# FeatherRemoteReceiverFullSMD.net
KiCad netlist of a schematic drawn in EAGLE
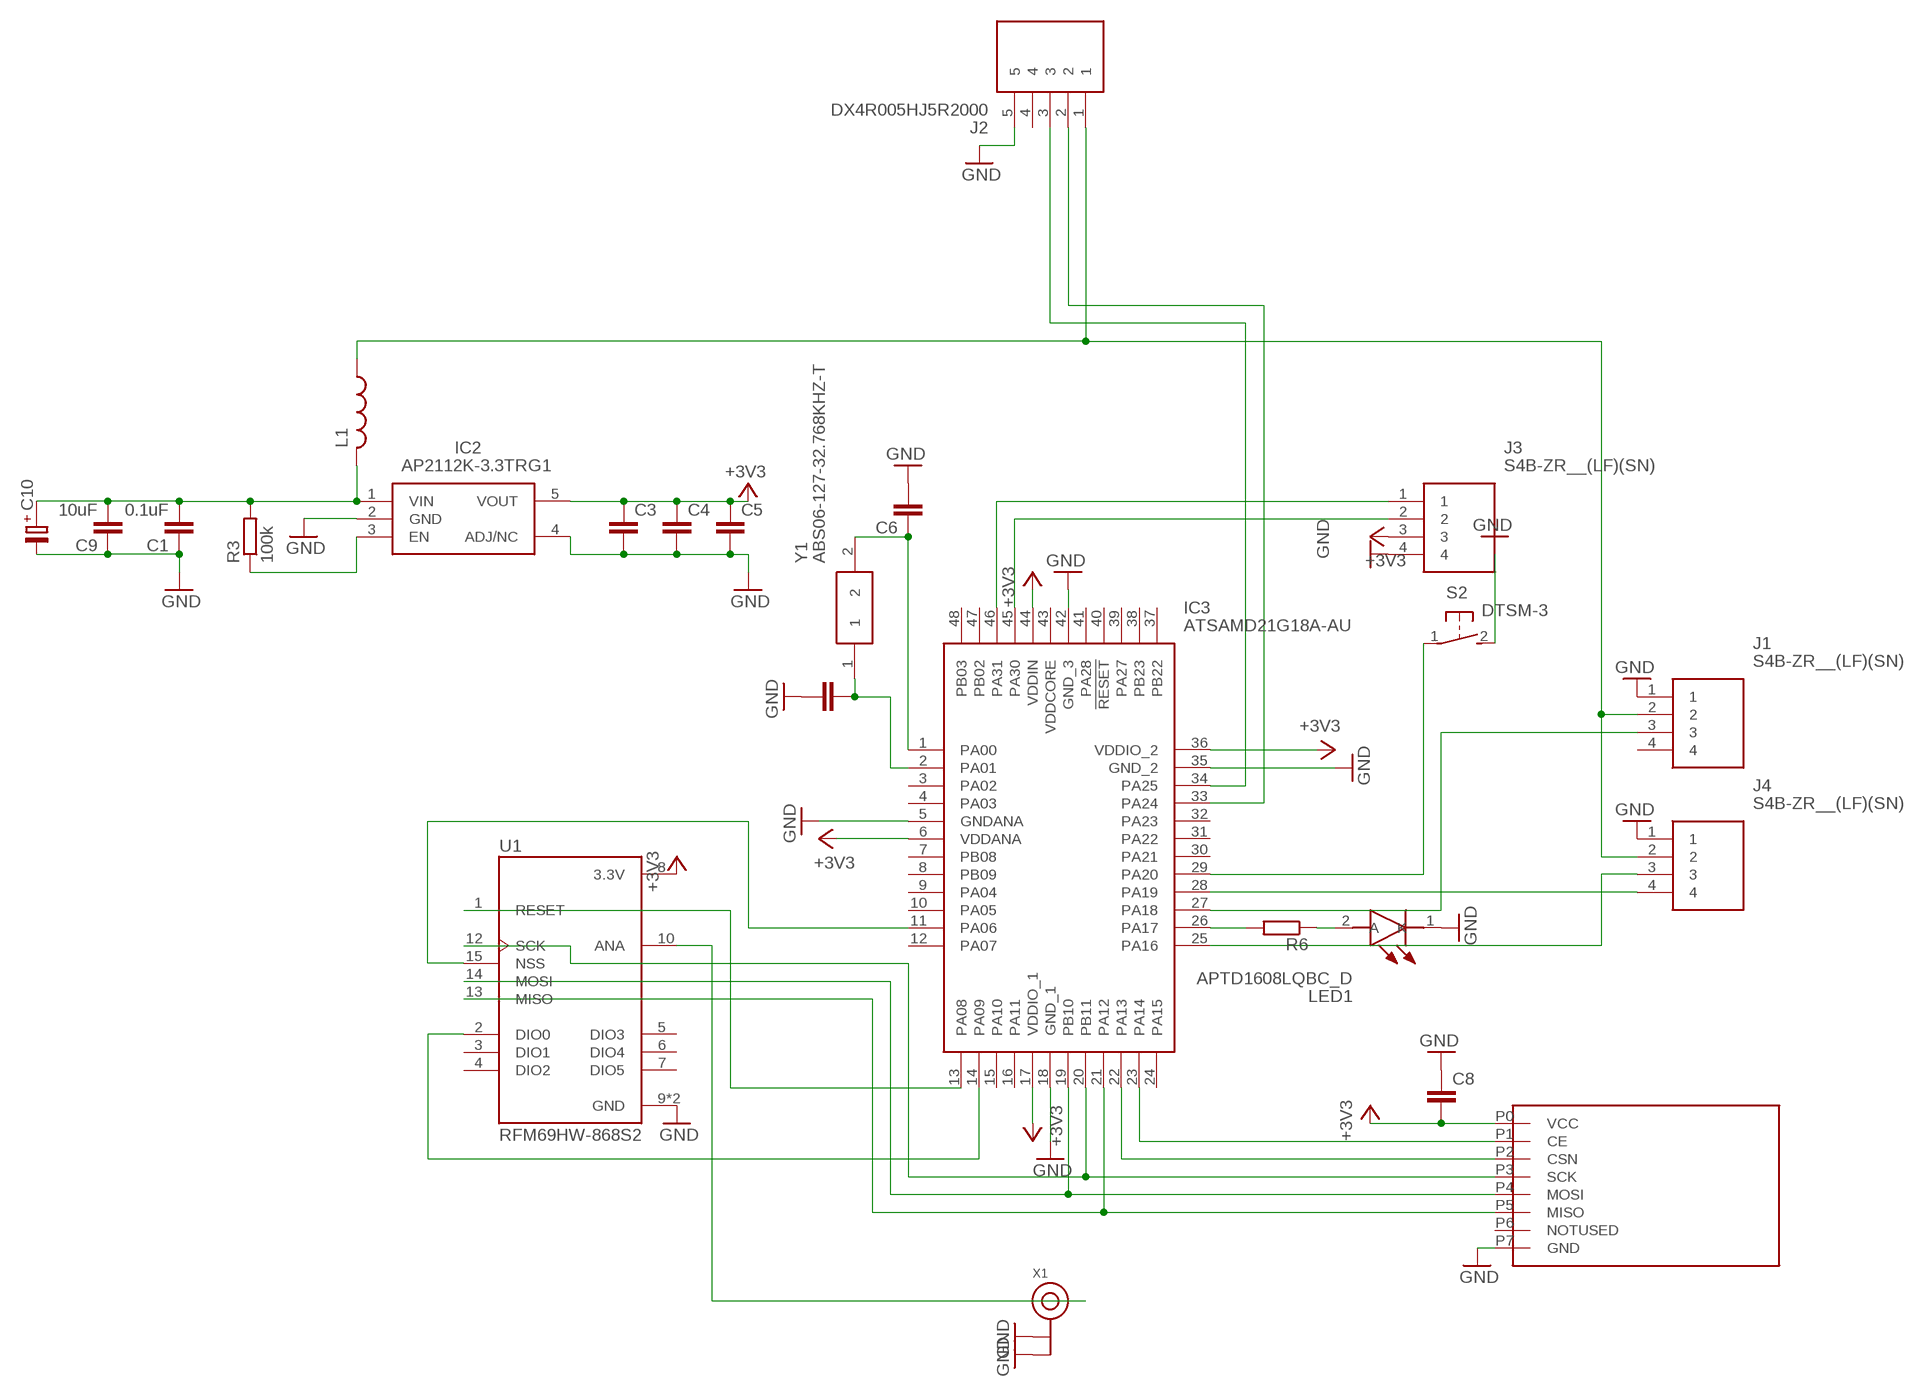
[diagram p0: schematic, sheet 1]

(export (version "E")
  (design (tool "Eeschema 10.0.6"))
  (components
    (comp (ref "C1")
      (value "0.1uF")
      (footprint "eagle-import:C0603")
      (libsource (lib "eagle-import") (part "C-EUC0603"))
    )
    (comp (ref "C3")
      (value "C-EUC0603")
      (footprint "eagle-import:C0603")
      (libsource (lib "eagle-import") (part "C-EUC0603"))
    )
    (comp (ref "C4")
      (value "C-EUC0603")
      (footprint "eagle-import:C0603")
      (libsource (lib "eagle-import") (part "C-EUC0603"))
    )
    (comp (ref "C5")
      (value "C-EUC0603")
      (footprint "eagle-import:C0603")
      (libsource (lib "eagle-import") (part "C-EUC0603"))
    )
    (comp (ref "C6")
      (value "C-EUC0603")
      (footprint "eagle-import:C0603")
      (libsource (lib "eagle-import") (part "C-EUC0603"))
    )
    (comp (ref "C7")
      (value "C-EUC0603")
      (footprint "eagle-import:C0603")
      (libsource (lib "eagle-import") (part "C-EUC0603"))
    )
    (comp (ref "C8")
      (value "C-EUC0603")
      (footprint "eagle-import:C0603")
      (libsource (lib "eagle-import") (part "C-EUC0603"))
    )
    (comp (ref "C9")
      (value "10uF")
      (footprint "eagle-import:C0603")
      (libsource (lib "eagle-import") (part "C-EUC0603"))
    )
    (comp (ref "C10")
      (value "C-PR-SMD-TE-D")
      (footprint "eagle-import:TE-D-7343")
      (libsource (lib "eagle-import") (part "C-PR-SMD-TE-D"))
    )
    (comp (ref "IC2")
      (value "AP2112K-3.3TRG1")
      (footprint "eagle-import:SOT95P282X130-5N")
      (fields (field (name "MOUSER_PART_NUMBER") "621-AP2112K-3.3TRG1"))
      (libsource (lib "eagle-import") (part "AP2112K-3.3TRG1"))
    )
    (comp (ref "IC3")
      (value "ATSAMD21G18A-AU")
      (footprint "eagle-import:QFP50P900X900X120-48N")
      (fields (field (name "MOUSER_PART_NUMBER") "556-ATSAMD21G18A-AU"))
      (libsource (lib "eagle-import") (part "ATSAMD21G18A-AU"))
    )
    (comp (ref "J1")
      (value "S4B-ZR__(LF)(SN)")
      (footprint "eagle-import:SHDR4W50P0X150_1X4_750X600X370")
      (fields (field (name "MANUFACTURER_PART_NUMBER") "S4B-ZR  (LF)(SN)"))
      (libsource (lib "eagle-import") (part "S4B-ZR__(LF)(SN)"))
    )
    (comp (ref "J2")
      (value "DX4R005HJ5R2000")
      (footprint "eagle-import:DX4R005HJ5")
      (fields (field (name "MOUSER_PART_NUMBER") "656-DX4R005HJ5R2000"))
      (libsource (lib "eagle-import") (part "DX4R005HJ5R2000"))
    )
    (comp (ref "J3")
      (value "S4B-ZR__(LF)(SN)")
      (footprint "eagle-import:SHDR4W50P0X150_1X4_750X600X370")
      (fields (field (name "MANUFACTURER_PART_NUMBER") "S4B-ZR  (LF)(SN)"))
      (libsource (lib "eagle-import") (part "S4B-ZR__(LF)(SN)"))
    )
    (comp (ref "J4")
      (value "S4B-ZR__(LF)(SN)")
      (footprint "eagle-import:SHDR4W50P0X150_1X4_750X600X370")
      (fields (field (name "MANUFACTURER_PART_NUMBER") "S4B-ZR  (LF)(SN)"))
      (libsource (lib "eagle-import") (part "S4B-ZR__(LF)(SN)"))
    )
    (comp (ref "L1")
      (value "L-USL1812")
      (footprint "eagle-import:L1812")
      (libsource (lib "eagle-import") (part "L-USL1812"))
    )
    (comp (ref "LED1")
      (value "APTD1608LQBC_D")
      (footprint "eagle-import:LEDC1608X95N")
      (fields
        (field (name "MANUFACTURER_PART_NUMBER") "APTD1608LQBC/D")
        (field (name "MOUSER_PART_NUMBER") "604-APTD1608LQBCD")
      )
      (libsource (lib "eagle-import") (part "APTD1608LQBC_D"))
    )
    (comp (ref "R3")
      (value "100k")
      (footprint "eagle-import:R0603")
      (libsource (lib "eagle-import") (part "R-EU_R0603"))
    )
    (comp (ref "R6")
      (value "R-EU_R0603")
      (footprint "eagle-import:R0603")
      (libsource (lib "eagle-import") (part "R-EU_R0603"))
    )
    (comp (ref "S2")
      (value "DTSM-3")
      (footprint "eagle-import:DTSM-3")
      (libsource (lib "eagle-import") (part "DTSM-3"))
    )
    (comp (ref "U$2")
      (value "NRF24L01PA")
      (footprint "eagle-import:NRF24L01PA")
      (libsource (lib "eagle-import") (part "NRF24L01PA"))
    )
    (comp (ref "U1")
      (value "RFM69HW-868S2")
      (footprint "eagle-import:XCVR_RFM69HW-868S2")
      (fields (field (name "MF") "RF"))
      (libsource (lib "eagle-import") (part "RFM69HW-868S2"))
    )
    (comp (ref "X1")
      (value "ANTENNA_U.FL")
      (footprint "eagle-import:U.FL")
      (libsource (lib "eagle-import") (part "ANTENNA_U.FL"))
    )
    (comp (ref "Y1")
      (value "ABS06-127-32.768KHZ-T")
      (footprint "eagle-import:ABS0612732768KHZT")
      (fields (field (name "MOUSER_PART_NUMBER") "815-ABS0612732.768KT"))
      (libsource (lib "eagle-import") (part "ABS06-127-32.768KHZ-T"))
    )
  )
  (nets
    (net (code "1") (name "+3V3") (class "Default")
      (node (ref "C3") (pin "1") (pinfunction "1_1") (pintype "passive"))
      (node (ref "C4") (pin "1") (pinfunction "1_1") (pintype "passive"))
      (node (ref "C5") (pin "1") (pinfunction "1_1") (pintype "passive"))
      (node (ref "C8") (pin "2") (pinfunction "2_2") (pintype "passive"))
      (node (ref "IC2") (pin "5") (pinfunction "VOUT_5") (pintype "bidirectional"))
      (node (ref "IC3") (pin "17") (pinfunction "VDDIO_1_17") (pintype "bidirectional"))
      (node (ref "IC3") (pin "36") (pinfunction "VDDIO_2_36") (pintype "bidirectional"))
      (node (ref "IC3") (pin "44") (pinfunction "VDDIN_44") (pintype "bidirectional"))
      (node (ref "IC3") (pin "6") (pinfunction "VDDANA_6") (pintype "bidirectional"))
      (node (ref "J3") (pin "3") (pinfunction "3_3") (pintype "bidirectional"))
      (node (ref "U$2") (pin "P0") (pinfunction "VCC_P0") (pintype "bidirectional"))
      (node (ref "U1") (pin "8") (pinfunction "3.3V_8") (pintype "power_in"))
    )
    (net (code "2") (name "GND") (class "Default")
      (node (ref "C1") (pin "1") (pinfunction "1_1") (pintype "passive"))
      (node (ref "C10") (pin "-") (pinfunction "-_-") (pintype "passive"))
      (node (ref "C3") (pin "2") (pinfunction "2_2") (pintype "passive"))
      (node (ref "C4") (pin "2") (pinfunction "2_2") (pintype "passive"))
      (node (ref "C5") (pin "2") (pinfunction "2_2") (pintype "passive"))
      (node (ref "C6") (pin "2") (pinfunction "2_2") (pintype "passive"))
      (node (ref "C7") (pin "1") (pinfunction "1_1") (pintype "passive"))
      (node (ref "C8") (pin "1") (pinfunction "1_1") (pintype "passive"))
      (node (ref "C9") (pin "1") (pinfunction "1_1") (pintype "passive"))
      (node (ref "IC2") (pin "2") (pinfunction "GND_2") (pintype "bidirectional"))
      (node (ref "IC2") (pin "4") (pinfunction "ADJ/NC_4") (pintype "bidirectional"))
      (node (ref "IC3") (pin "18") (pinfunction "GND_1_18") (pintype "bidirectional"))
      (node (ref "IC3") (pin "35") (pinfunction "GND_2_35") (pintype "bidirectional"))
      (node (ref "IC3") (pin "42") (pinfunction "GND_3_42") (pintype "bidirectional"))
      (node (ref "IC3") (pin "5") (pinfunction "GNDANA_5") (pintype "bidirectional"))
      (node (ref "J1") (pin "1") (pinfunction "1_1") (pintype "bidirectional"))
      (node (ref "J2") (pin "5") (pinfunction "5_5") (pintype "bidirectional"))
      (node (ref "J3") (pin "4") (pinfunction "4_4") (pintype "bidirectional"))
      (node (ref "J4") (pin "1") (pinfunction "1_1") (pintype "bidirectional"))
      (node (ref "LED1") (pin "1") (pinfunction "K_1") (pintype "bidirectional"))
      (node (ref "S2") (pin "2") (pinfunction "2_2") (pintype "passive"))
      (node (ref "U$2") (pin "P7") (pinfunction "GND_P7") (pintype "bidirectional"))
      (node (ref "U1") (pin "11") (pinfunction "GND_11") (pintype "power_in"))
      (node (ref "U1") (pin "9") (pinfunction "GND_9") (pintype "power_in"))
      (node (ref "X1") (pin "1") (pinfunction "GND_1") (pintype "passive"))
      (node (ref "X1") (pin "2") (pinfunction "GND_2") (pintype "passive"))
    )
    (net (code "3") (name "Net-(IC2-EN)") (class "Default")
      (node (ref "IC2") (pin "3") (pinfunction "EN_3") (pintype "bidirectional"))
      (node (ref "R3") (pin "1") (pinfunction "1_1") (pintype "passive"))
    )
    (net (code "4") (name "Net-(IC2-VIN)") (class "Default")
      (node (ref "C1") (pin "2") (pinfunction "2_2") (pintype "passive"))
      (node (ref "C10") (pin "+") (pinfunction "+_+") (pintype "passive"))
      (node (ref "C9") (pin "2") (pinfunction "2_2") (pintype "passive"))
      (node (ref "IC2") (pin "1") (pinfunction "VIN_1") (pintype "bidirectional"))
      (node (ref "L1") (pin "2") (pinfunction "2_2") (pintype "passive"))
      (node (ref "R3") (pin "2") (pinfunction "2_2") (pintype "passive"))
    )
    (net (code "5") (name "Net-(IC3-PA00)") (class "Default")
      (node (ref "C6") (pin "1") (pinfunction "1_1") (pintype "passive"))
      (node (ref "IC3") (pin "1") (pinfunction "PA00_1") (pintype "bidirectional"))
      (node (ref "Y1") (pin "2") (pinfunction "2_2") (pintype "bidirectional"))
    )
    (net (code "6") (name "Net-(IC3-PA01)") (class "Default")
      (node (ref "C7") (pin "2") (pinfunction "2_2") (pintype "passive"))
      (node (ref "IC3") (pin "2") (pinfunction "PA01_2") (pintype "bidirectional"))
      (node (ref "Y1") (pin "1") (pinfunction "1_1") (pintype "bidirectional"))
    )
    (net (code "7") (name "Net-(IC3-PA06)") (class "Default")
      (node (ref "IC3") (pin "11") (pinfunction "PA06_11") (pintype "bidirectional"))
      (node (ref "U1") (pin "15") (pinfunction "NSS_15") (pintype "input"))
    )
    (net (code "8") (name "Net-(IC3-PA08)") (class "Default")
      (node (ref "IC3") (pin "13") (pinfunction "PA08_13") (pintype "bidirectional"))
      (node (ref "U1") (pin "1") (pinfunction "RESET_1") (pintype "bidirectional"))
    )
    (net (code "9") (name "Net-(IC3-PA09)") (class "Default")
      (node (ref "IC3") (pin "14") (pinfunction "PA09_14") (pintype "bidirectional"))
      (node (ref "U1") (pin "2") (pinfunction "DIO0_2") (pintype "bidirectional"))
    )
    (net (code "10") (name "Net-(IC3-PA12)") (class "Default")
      (node (ref "IC3") (pin "21") (pinfunction "PA12_21") (pintype "bidirectional"))
      (node (ref "U$2") (pin "P5") (pinfunction "MISO_P5") (pintype "bidirectional"))
      (node (ref "U1") (pin "13") (pinfunction "MISO_13") (pintype "output"))
    )
    (net (code "11") (name "Net-(IC3-PA13)") (class "Default")
      (node (ref "IC3") (pin "22") (pinfunction "PA13_22") (pintype "bidirectional"))
      (node (ref "U$2") (pin "P2") (pinfunction "CSN_P2") (pintype "bidirectional"))
    )
    (net (code "12") (name "Net-(IC3-PA14)") (class "Default")
      (node (ref "IC3") (pin "23") (pinfunction "PA14_23") (pintype "bidirectional"))
      (node (ref "U$2") (pin "P1") (pinfunction "CE_P1") (pintype "bidirectional"))
    )
    (net (code "13") (name "Net-(IC3-PA16)") (class "Default")
      (node (ref "IC3") (pin "25") (pinfunction "PA16_25") (pintype "bidirectional"))
      (node (ref "J4") (pin "3") (pinfunction "3_3") (pintype "bidirectional"))
    )
    (net (code "14") (name "Net-(IC3-PA17)") (class "Default")
      (node (ref "IC3") (pin "26") (pinfunction "PA17_26") (pintype "bidirectional"))
      (node (ref "R6") (pin "2") (pinfunction "2_2") (pintype "passive"))
    )
    (net (code "15") (name "Net-(IC3-PA18)") (class "Default")
      (node (ref "IC3") (pin "27") (pinfunction "PA18_27") (pintype "bidirectional"))
      (node (ref "J1") (pin "3") (pinfunction "3_3") (pintype "bidirectional"))
    )
    (net (code "16") (name "Net-(IC3-PA19)") (class "Default")
      (node (ref "IC3") (pin "28") (pinfunction "PA19_28") (pintype "bidirectional"))
      (node (ref "J4") (pin "4") (pinfunction "4_4") (pintype "bidirectional"))
    )
    (net (code "17") (name "Net-(IC3-PA20)") (class "Default")
      (node (ref "IC3") (pin "29") (pinfunction "PA20_29") (pintype "bidirectional"))
      (node (ref "S2") (pin "1") (pinfunction "1_1") (pintype "passive"))
    )
    (net (code "18") (name "Net-(IC3-PA24)") (class "Default")
      (node (ref "IC3") (pin "33") (pinfunction "PA24_33") (pintype "bidirectional"))
      (node (ref "J2") (pin "2") (pinfunction "2_2") (pintype "bidirectional"))
    )
    (net (code "19") (name "Net-(IC3-PA25)") (class "Default")
      (node (ref "IC3") (pin "34") (pinfunction "PA25_34") (pintype "bidirectional"))
      (node (ref "J2") (pin "3") (pinfunction "3_3") (pintype "bidirectional"))
    )
    (net (code "20") (name "Net-(IC3-PA30)") (class "Default")
      (node (ref "IC3") (pin "45") (pinfunction "PA30_45") (pintype "bidirectional"))
      (node (ref "J3") (pin "2") (pinfunction "2_2") (pintype "bidirectional"))
    )
    (net (code "21") (name "Net-(IC3-PA31)") (class "Default")
      (node (ref "IC3") (pin "46") (pinfunction "PA31_46") (pintype "bidirectional"))
      (node (ref "J3") (pin "1") (pinfunction "1_1") (pintype "bidirectional"))
    )
    (net (code "22") (name "Net-(IC3-PB10)") (class "Default")
      (node (ref "IC3") (pin "19") (pinfunction "PB10_19") (pintype "bidirectional"))
      (node (ref "U$2") (pin "P4") (pinfunction "MOSI_P4") (pintype "bidirectional"))
      (node (ref "U1") (pin "14") (pinfunction "MOSI_14") (pintype "input"))
    )
    (net (code "23") (name "Net-(IC3-PB11)") (class "Default")
      (node (ref "IC3") (pin "20") (pinfunction "PB11_20") (pintype "bidirectional"))
      (node (ref "U$2") (pin "P3") (pinfunction "SCK_P3") (pintype "bidirectional"))
      (node (ref "U1") (pin "12") (pinfunction "SCK_12") (pintype "input"))
    )
    (net (code "24") (name "Net-(J1-Pad2)") (class "Default")
      (node (ref "J1") (pin "2") (pinfunction "2_2") (pintype "bidirectional"))
      (node (ref "J2") (pin "1") (pinfunction "1_1") (pintype "bidirectional"))
      (node (ref "J4") (pin "2") (pinfunction "2_2") (pintype "bidirectional"))
      (node (ref "L1") (pin "1") (pinfunction "1_1") (pintype "passive"))
    )
    (net (code "25") (name "Net-(LED1-A)") (class "Default")
      (node (ref "LED1") (pin "2") (pinfunction "A_2") (pintype "bidirectional"))
      (node (ref "R6") (pin "1") (pinfunction "1_1") (pintype "passive"))
    )
    (net (code "26") (name "Net-(U1-ANA)") (class "Default")
      (node (ref "U1") (pin "10") (pinfunction "ANA_10") (pintype "bidirectional"))
      (node (ref "X1") (pin "3") (pinfunction "SIGNAL_3") (pintype "passive"))
    )
    (net (code "27") (name "unconnected-(IC3-PA02-Pad3)") (class "Default")
      (node (ref "IC3") (pin "3") (pinfunction "PA02_3") (pintype "bidirectional"))
    )
    (net (code "28") (name "unconnected-(IC3-PA03-Pad4)") (class "Default")
      (node (ref "IC3") (pin "4") (pinfunction "PA03_4") (pintype "bidirectional"))
    )
    (net (code "29") (name "unconnected-(IC3-PA04-Pad9)") (class "Default")
      (node (ref "IC3") (pin "9") (pinfunction "PA04_9") (pintype "bidirectional"))
    )
    (net (code "30") (name "unconnected-(IC3-PA05-Pad10)") (class "Default")
      (node (ref "IC3") (pin "10") (pinfunction "PA05_10") (pintype "bidirectional"))
    )
    (net (code "31") (name "unconnected-(IC3-PA07-Pad12)") (class "Default")
      (node (ref "IC3") (pin "12") (pinfunction "PA07_12") (pintype "bidirectional"))
    )
    (net (code "32") (name "unconnected-(IC3-PA10-Pad15)") (class "Default")
      (node (ref "IC3") (pin "15") (pinfunction "PA10_15") (pintype "bidirectional"))
    )
    (net (code "33") (name "unconnected-(IC3-PA11-Pad16)") (class "Default")
      (node (ref "IC3") (pin "16") (pinfunction "PA11_16") (pintype "bidirectional"))
    )
    (net (code "34") (name "unconnected-(IC3-PA15-Pad24)") (class "Default")
      (node (ref "IC3") (pin "24") (pinfunction "PA15_24") (pintype "bidirectional"))
    )
    (net (code "35") (name "unconnected-(IC3-PA21-Pad30)") (class "Default")
      (node (ref "IC3") (pin "30") (pinfunction "PA21_30") (pintype "bidirectional"))
    )
    (net (code "36") (name "unconnected-(IC3-PA22-Pad31)") (class "Default")
      (node (ref "IC3") (pin "31") (pinfunction "PA22_31") (pintype "bidirectional"))
    )
    (net (code "37") (name "unconnected-(IC3-PA23-Pad32)") (class "Default")
      (node (ref "IC3") (pin "32") (pinfunction "PA23_32") (pintype "bidirectional"))
    )
    (net (code "38") (name "unconnected-(IC3-PA27-Pad39)") (class "Default")
      (node (ref "IC3") (pin "39") (pinfunction "PA27_39") (pintype "bidirectional"))
    )
    (net (code "39") (name "unconnected-(IC3-PA28-Pad41)") (class "Default")
      (node (ref "IC3") (pin "41") (pinfunction "PA28_41") (pintype "bidirectional"))
    )
    (net (code "40") (name "unconnected-(IC3-PB02-Pad47)") (class "Default")
      (node (ref "IC3") (pin "47") (pinfunction "PB02_47") (pintype "bidirectional"))
    )
    (net (code "41") (name "unconnected-(IC3-PB03-Pad48)") (class "Default")
      (node (ref "IC3") (pin "48") (pinfunction "PB03_48") (pintype "bidirectional"))
    )
    (net (code "42") (name "unconnected-(IC3-PB08-Pad7)") (class "Default")
      (node (ref "IC3") (pin "7") (pinfunction "PB08_7") (pintype "bidirectional"))
    )
    (net (code "43") (name "unconnected-(IC3-PB09-Pad8)") (class "Default")
      (node (ref "IC3") (pin "8") (pinfunction "PB09_8") (pintype "bidirectional"))
    )
    (net (code "44") (name "unconnected-(IC3-PB22-Pad37)") (class "Default")
      (node (ref "IC3") (pin "37") (pinfunction "PB22_37") (pintype "bidirectional"))
    )
    (net (code "45") (name "unconnected-(IC3-PB23-Pad38)") (class "Default")
      (node (ref "IC3") (pin "38") (pinfunction "PB23_38") (pintype "bidirectional"))
    )
    (net (code "46") (name "unconnected-(IC3-VDDCORE-Pad43)") (class "Default")
      (node (ref "IC3") (pin "43") (pinfunction "VDDCORE_43") (pintype "bidirectional"))
    )
    (net (code "47") (name "unconnected-(IC3-~{RESET}-Pad40)") (class "Default")
      (node (ref "IC3") (pin "40") (pinfunction "~{RESET}_40") (pintype "bidirectional"))
    )
    (net (code "48") (name "unconnected-(J1-Pad4)") (class "Default")
      (node (ref "J1") (pin "4") (pinfunction "4_4") (pintype "bidirectional"))
    )
    (net (code "49") (name "unconnected-(J2-Pad4)") (class "Default")
      (node (ref "J2") (pin "4") (pinfunction "4_4") (pintype "bidirectional"))
    )
    (net (code "50") (name "unconnected-(U$2-NOTUSED-PadP6)") (class "Default")
      (node (ref "U$2") (pin "P6") (pinfunction "NOTUSED_P6") (pintype "bidirectional"))
    )
    (net (code "51") (name "unconnected-(U1-DIO1-Pad3)") (class "Default")
      (node (ref "U1") (pin "3") (pinfunction "DIO1_3") (pintype "bidirectional"))
    )
    (net (code "52") (name "unconnected-(U1-DIO2-Pad4)") (class "Default")
      (node (ref "U1") (pin "4") (pinfunction "DIO2_4") (pintype "bidirectional"))
    )
    (net (code "53") (name "unconnected-(U1-DIO3-Pad5)") (class "Default")
      (node (ref "U1") (pin "5") (pinfunction "DIO3_5") (pintype "bidirectional"))
    )
    (net (code "54") (name "unconnected-(U1-DIO4-Pad6)") (class "Default")
      (node (ref "U1") (pin "6") (pinfunction "DIO4_6") (pintype "bidirectional"))
    )
    (net (code "55") (name "unconnected-(U1-DIO5-Pad7)") (class "Default")
      (node (ref "U1") (pin "7") (pinfunction "DIO5_7") (pintype "bidirectional"))
    )
  )
)
